# mcremote.net
KiCad netlist of a schematic drawn in EAGLE
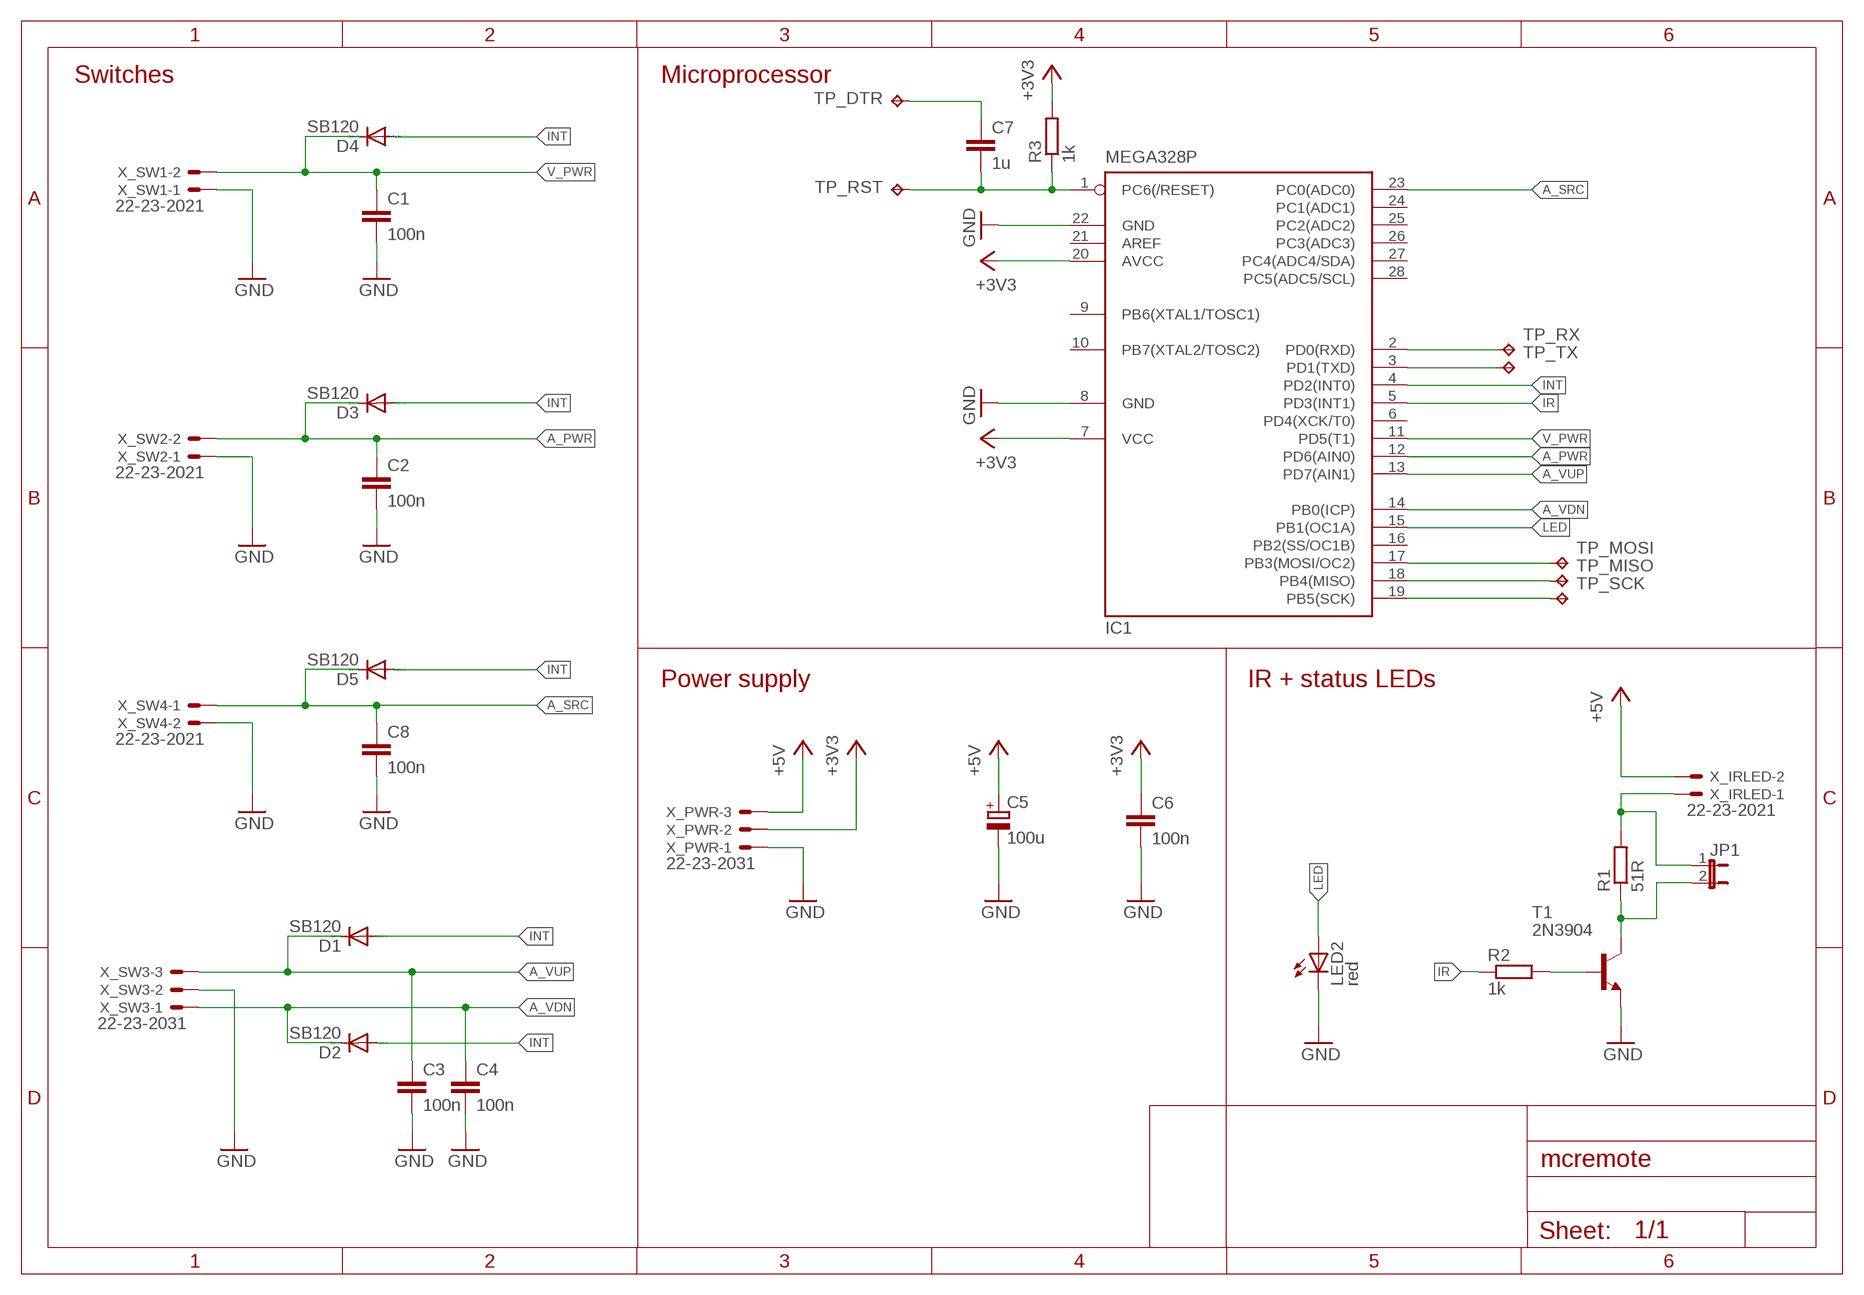
[diagram p0: schematic, sheet 1]

(export (version "E")
  (design (tool "Eeschema 10.0.6"))
  (components
    (comp (ref "C1")
      (value "100n")
      (footprint "eagle-import:C025-024X044")
      (libsource (lib "eagle-import") (part "C-EU025-024X044"))
    )
    (comp (ref "C2")
      (value "100n")
      (footprint "eagle-import:C025-024X044")
      (libsource (lib "eagle-import") (part "C-EU025-024X044"))
    )
    (comp (ref "C3")
      (value "100n")
      (footprint "eagle-import:C025-024X044")
      (libsource (lib "eagle-import") (part "C-EU025-024X044"))
    )
    (comp (ref "C4")
      (value "100n")
      (footprint "eagle-import:C025-024X044")
      (libsource (lib "eagle-import") (part "C-EU025-024X044"))
    )
    (comp (ref "C5")
      (value "100u")
      (footprint "eagle-import:E3,5-8")
      (libsource (lib "eagle-import") (part "CPOL-EUE3.5-8"))
    )
    (comp (ref "C6")
      (value "100n")
      (footprint "eagle-import:C025-024X044")
      (libsource (lib "eagle-import") (part "C-EU025-024X044"))
    )
    (comp (ref "C7")
      (value "1u")
      (footprint "eagle-import:C025-024X044")
      (libsource (lib "eagle-import") (part "C-EU025-024X044"))
    )
    (comp (ref "C8")
      (value "100n")
      (footprint "eagle-import:C025-024X044")
      (libsource (lib "eagle-import") (part "C-EU025-024X044"))
    )
    (comp (ref "D1")
      (value "SB120")
      (footprint "eagle-import:DO41-10")
      (libsource (lib "eagle-import") (part "SB120"))
    )
    (comp (ref "D2")
      (value "SB120")
      (footprint "eagle-import:DO41-10")
      (libsource (lib "eagle-import") (part "SB120"))
    )
    (comp (ref "D3")
      (value "SB120")
      (footprint "eagle-import:DO41-10")
      (libsource (lib "eagle-import") (part "SB120"))
    )
    (comp (ref "D4")
      (value "SB120")
      (footprint "eagle-import:DO41-10")
      (libsource (lib "eagle-import") (part "SB120"))
    )
    (comp (ref "D5")
      (value "SB120")
      (footprint "eagle-import:DO41-7.6")
      (libsource (lib "eagle-import") (part "DIODE-DO41-7.6"))
    )
    (comp (ref "IC1")
      (value "MEGA328P")
      (footprint "eagle-import:DIL28-3")
      (libsource (lib "eagle-import") (part "MEGA8-P"))
    )
    (comp (ref "JP1")
      (value "JP1E")
      (footprint "eagle-import:JP1")
      (libsource (lib "eagle-import") (part "JP1E"))
    )
    (comp (ref "LED2")
      (value "red")
      (footprint "eagle-import:LED3MM")
      (libsource (lib "eagle-import") (part "LED3MM"))
    )
    (comp (ref "R1")
      (value "51R")
      (footprint "eagle-import:0207_7")
      (libsource (lib "eagle-import") (part "R-EU_0207/7"))
    )
    (comp (ref "R2")
      (value "1k")
      (footprint "eagle-import:0207_7")
      (libsource (lib "eagle-import") (part "R-EU_0207/7"))
    )
    (comp (ref "R3")
      (value "1k")
      (footprint "eagle-import:0207_7")
      (libsource (lib "eagle-import") (part "R-EU_0207/7"))
    )
    (comp (ref "T1")
      (value "2N3904")
      (footprint "eagle-import:TO92")
      (libsource (lib "eagle-import") (part "2N3904"))
    )
    (comp (ref "TP_DTR")
      (value "TPPAD1-13")
      (footprint "eagle-import:P1-13")
      (libsource (lib "eagle-import") (part "TPPAD1-13"))
    )
    (comp (ref "TP_MISO")
      (value "TPPAD1-13")
      (footprint "eagle-import:P1-13")
      (libsource (lib "eagle-import") (part "TPPAD1-13"))
    )
    (comp (ref "TP_MOSI")
      (value "TPPAD1-13")
      (footprint "eagle-import:P1-13")
      (libsource (lib "eagle-import") (part "TPPAD1-13"))
    )
    (comp (ref "TP_RST")
      (value "TPPAD1-13")
      (footprint "eagle-import:P1-13")
      (libsource (lib "eagle-import") (part "TPPAD1-13"))
    )
    (comp (ref "TP_RX")
      (value "TPPAD1-13")
      (footprint "eagle-import:P1-13")
      (libsource (lib "eagle-import") (part "TPPAD1-13"))
    )
    (comp (ref "TP_SCK")
      (value "TPPAD1-13")
      (footprint "eagle-import:P1-13")
      (libsource (lib "eagle-import") (part "TPPAD1-13"))
    )
    (comp (ref "TP_TX")
      (value "TPPAD1-13")
      (footprint "eagle-import:P1-13")
      (libsource (lib "eagle-import") (part "TPPAD1-13"))
    )
    (comp (ref "X_IRLED")
      (value "22-23-2021")
      (footprint "eagle-import:22-23-2021")
      (fields (field (name "MF") "MOLEX"))
      (libsource (lib "eagle-import") (part "22-23-2021"))
    )
    (comp (ref "X_PWR")
      (value "22-23-2031")
      (footprint "eagle-import:22-23-2031")
      (fields (field (name "MF") "MOLEX"))
      (libsource (lib "eagle-import") (part "22-23-2031"))
    )
    (comp (ref "X_SW1")
      (value "22-23-2021")
      (footprint "eagle-import:22-23-2021")
      (fields (field (name "MF") "MOLEX"))
      (libsource (lib "eagle-import") (part "22-23-2021"))
    )
    (comp (ref "X_SW2")
      (value "22-23-2021")
      (footprint "eagle-import:22-23-2021")
      (fields (field (name "MF") "MOLEX"))
      (libsource (lib "eagle-import") (part "22-23-2021"))
    )
    (comp (ref "X_SW3")
      (value "22-23-2031")
      (footprint "eagle-import:22-23-2031")
      (fields (field (name "MF") "MOLEX"))
      (libsource (lib "eagle-import") (part "22-23-2031"))
    )
    (comp (ref "X_SW4")
      (value "22-23-2021")
      (footprint "eagle-import:22-23-2021")
      (fields (field (name "MF") "MOLEX"))
      (libsource (lib "eagle-import") (part "22-23-2021"))
    )
  )
  (nets
    (net (code "1") (name "+3V3") (class "Default")
      (node (ref "C6") (pin "1") (pinfunction "1_1") (pintype "passive"))
      (node (ref "IC1") (pin "20") (pinfunction "AVCC_20") (pintype "power_in"))
      (node (ref "IC1") (pin "7") (pinfunction "VCC_7") (pintype "power_in"))
      (node (ref "R3") (pin "2") (pinfunction "2_2") (pintype "passive"))
      (node (ref "X_PWR") (pin "2") (pinfunction "S_2") (pintype "passive"))
    )
    (net (code "2") (name "+5V") (class "Default")
      (node (ref "C5") (pin "+") (pinfunction "+_+") (pintype "passive"))
      (node (ref "X_IRLED") (pin "2") (pinfunction "S_2") (pintype "passive"))
      (node (ref "X_PWR") (pin "3") (pinfunction "S_3") (pintype "passive"))
    )
    (net (code "3") (name "A_PWR") (class "Default")
      (node (ref "C2") (pin "1") (pinfunction "1_1") (pintype "passive"))
      (node (ref "D3") (pin "C") (pinfunction "C_C") (pintype "passive"))
      (node (ref "IC1") (pin "12") (pinfunction "PD6(AIN0)_12") (pintype "bidirectional"))
      (node (ref "X_SW2") (pin "2") (pinfunction "S_2") (pintype "passive"))
    )
    (net (code "4") (name "A_SRC") (class "Default")
      (node (ref "C8") (pin "1") (pinfunction "1_1") (pintype "passive"))
      (node (ref "D5") (pin "C") (pinfunction "C_C") (pintype "passive"))
      (node (ref "IC1") (pin "23") (pinfunction "PC0(ADC0)_23") (pintype "bidirectional"))
      (node (ref "X_SW4") (pin "1") (pinfunction "S_1") (pintype "passive"))
    )
    (net (code "5") (name "A_VDN") (class "Default")
      (node (ref "C4") (pin "1") (pinfunction "1_1") (pintype "passive"))
      (node (ref "D2") (pin "C") (pinfunction "C_C") (pintype "passive"))
      (node (ref "IC1") (pin "14") (pinfunction "PB0(ICP)_14") (pintype "bidirectional"))
      (node (ref "X_SW3") (pin "1") (pinfunction "S_1") (pintype "passive"))
    )
    (net (code "6") (name "A_VUP") (class "Default")
      (node (ref "C3") (pin "1") (pinfunction "1_1") (pintype "passive"))
      (node (ref "D1") (pin "C") (pinfunction "C_C") (pintype "passive"))
      (node (ref "IC1") (pin "13") (pinfunction "PD7(AIN1)_13") (pintype "bidirectional"))
      (node (ref "X_SW3") (pin "3") (pinfunction "S_3") (pintype "passive"))
    )
    (net (code "7") (name "GND") (class "Default")
      (node (ref "C1") (pin "2") (pinfunction "2_2") (pintype "passive"))
      (node (ref "C2") (pin "2") (pinfunction "2_2") (pintype "passive"))
      (node (ref "C3") (pin "2") (pinfunction "2_2") (pintype "passive"))
      (node (ref "C4") (pin "2") (pinfunction "2_2") (pintype "passive"))
      (node (ref "C5") (pin "-") (pinfunction "-_-") (pintype "passive"))
      (node (ref "C6") (pin "2") (pinfunction "2_2") (pintype "passive"))
      (node (ref "C8") (pin "2") (pinfunction "2_2") (pintype "passive"))
      (node (ref "IC1") (pin "22") (pinfunction "GND_22") (pintype "power_in"))
      (node (ref "IC1") (pin "8") (pinfunction "GND_8") (pintype "power_in"))
      (node (ref "LED2") (pin "K") (pinfunction "C_K") (pintype "passive"))
      (node (ref "T1") (pin "3") (pinfunction "E_3") (pintype "passive"))
      (node (ref "X_PWR") (pin "1") (pinfunction "S_1") (pintype "passive"))
      (node (ref "X_SW1") (pin "1") (pinfunction "S_1") (pintype "passive"))
      (node (ref "X_SW2") (pin "1") (pinfunction "S_1") (pintype "passive"))
      (node (ref "X_SW3") (pin "2") (pinfunction "S_2") (pintype "passive"))
      (node (ref "X_SW4") (pin "2") (pinfunction "S_2") (pintype "passive"))
    )
    (net (code "8") (name "INT") (class "Default")
      (node (ref "D1") (pin "A") (pinfunction "A_A") (pintype "passive"))
      (node (ref "D2") (pin "A") (pinfunction "A_A") (pintype "passive"))
      (node (ref "D3") (pin "A") (pinfunction "A_A") (pintype "passive"))
      (node (ref "D4") (pin "A") (pinfunction "A_A") (pintype "passive"))
      (node (ref "D5") (pin "A") (pinfunction "A_A") (pintype "passive"))
      (node (ref "IC1") (pin "4") (pinfunction "PD2(INT0)_4") (pintype "bidirectional"))
    )
    (net (code "9") (name "IR") (class "Default")
      (node (ref "IC1") (pin "5") (pinfunction "PD3(INT1)_5") (pintype "bidirectional"))
      (node (ref "R2") (pin "1") (pinfunction "1_1") (pintype "passive"))
    )
    (net (code "10") (name "LED") (class "Default")
      (node (ref "IC1") (pin "15") (pinfunction "PB1(OC1A)_15") (pintype "bidirectional"))
      (node (ref "LED2") (pin "A") (pinfunction "A_A") (pintype "passive"))
    )
    (net (code "11") (name "Net-(C7-Pad1)") (class "Default")
      (node (ref "C7") (pin "1") (pinfunction "1_1") (pintype "passive"))
      (node (ref "TP_DTR") (pin "TP") (pinfunction "TP_TP") (pintype "input"))
    )
    (net (code "12") (name "Net-(IC1-PB3(MOSI{slash}OC2))") (class "Default")
      (node (ref "IC1") (pin "17") (pinfunction "PB3(MOSI/OC2)_17") (pintype "bidirectional"))
      (node (ref "TP_MOSI") (pin "TP") (pinfunction "TP_TP") (pintype "input"))
    )
    (net (code "13") (name "Net-(IC1-PB4(MISO))") (class "Default")
      (node (ref "IC1") (pin "18") (pinfunction "PB4(MISO)_18") (pintype "bidirectional"))
      (node (ref "TP_MISO") (pin "TP") (pinfunction "TP_TP") (pintype "input"))
    )
    (net (code "14") (name "Net-(IC1-PB5(SCK))") (class "Default")
      (node (ref "IC1") (pin "19") (pinfunction "PB5(SCK)_19") (pintype "bidirectional"))
      (node (ref "TP_SCK") (pin "TP") (pinfunction "TP_TP") (pintype "input"))
    )
    (net (code "15") (name "Net-(IC1-PC6({slash}RESET))") (class "Default")
      (node (ref "C7") (pin "2") (pinfunction "2_2") (pintype "passive"))
      (node (ref "IC1") (pin "1") (pinfunction "PC6(/RESET)_1") (pintype "bidirectional"))
      (node (ref "R3") (pin "1") (pinfunction "1_1") (pintype "passive"))
      (node (ref "TP_RST") (pin "TP") (pinfunction "TP_TP") (pintype "input"))
    )
    (net (code "16") (name "Net-(IC1-PD0(RXD))") (class "Default")
      (node (ref "IC1") (pin "2") (pinfunction "PD0(RXD)_2") (pintype "bidirectional"))
      (node (ref "TP_RX") (pin "TP") (pinfunction "TP_TP") (pintype "input"))
    )
    (net (code "17") (name "Net-(IC1-PD1(TXD))") (class "Default")
      (node (ref "IC1") (pin "3") (pinfunction "PD1(TXD)_3") (pintype "bidirectional"))
      (node (ref "TP_TX") (pin "TP") (pinfunction "TP_TP") (pintype "input"))
    )
    (net (code "18") (name "Net-(T1-B)") (class "Default")
      (node (ref "R2") (pin "2") (pinfunction "2_2") (pintype "passive"))
      (node (ref "T1") (pin "2") (pinfunction "B_2") (pintype "passive"))
    )
    (net (code "19") (name "Net-(T1-C)") (class "Default")
      (node (ref "JP1") (pin "2") (pinfunction "2_2") (pintype "passive"))
      (node (ref "R1") (pin "1") (pinfunction "1_1") (pintype "passive"))
      (node (ref "T1") (pin "1") (pinfunction "C_1") (pintype "passive"))
    )
    (net (code "20") (name "Net-(X_IRLEDA-S)") (class "Default")
      (node (ref "JP1") (pin "1") (pinfunction "1_1") (pintype "passive"))
      (node (ref "R1") (pin "2") (pinfunction "2_2") (pintype "passive"))
      (node (ref "X_IRLED") (pin "1") (pinfunction "S_1") (pintype "passive"))
    )
    (net (code "21") (name "V_PWR") (class "Default")
      (node (ref "C1") (pin "1") (pinfunction "1_1") (pintype "passive"))
      (node (ref "D4") (pin "C") (pinfunction "C_C") (pintype "passive"))
      (node (ref "IC1") (pin "11") (pinfunction "PD5(T1)_11") (pintype "bidirectional"))
      (node (ref "X_SW1") (pin "2") (pinfunction "S_2") (pintype "passive"))
    )
    (net (code "22") (name "unconnected-(IC1-AREF-Pad21)") (class "Default")
      (node (ref "IC1") (pin "21") (pinfunction "AREF_21") (pintype "passive"))
    )
    (net (code "23") (name "unconnected-(IC1-PB2(SS{slash}OC1B)-Pad16)") (class "Default")
      (node (ref "IC1") (pin "16") (pinfunction "PB2(SS/OC1B)_16") (pintype "bidirectional"))
    )
    (net (code "24") (name "unconnected-(IC1-PB6(XTAL1{slash}TOSC1)-Pad9)") (class "Default")
      (node (ref "IC1") (pin "9") (pinfunction "PB6(XTAL1/TOSC1)_9") (pintype "bidirectional"))
    )
    (net (code "25") (name "unconnected-(IC1-PB7(XTAL2{slash}TOSC2)-Pad10)") (class "Default")
      (node (ref "IC1") (pin "10") (pinfunction "PB7(XTAL2/TOSC2)_10") (pintype "bidirectional"))
    )
    (net (code "26") (name "unconnected-(IC1-PC1(ADC1)-Pad24)") (class "Default")
      (node (ref "IC1") (pin "24") (pinfunction "PC1(ADC1)_24") (pintype "bidirectional"))
    )
    (net (code "27") (name "unconnected-(IC1-PC2(ADC2)-Pad25)") (class "Default")
      (node (ref "IC1") (pin "25") (pinfunction "PC2(ADC2)_25") (pintype "bidirectional"))
    )
    (net (code "28") (name "unconnected-(IC1-PC3(ADC3)-Pad26)") (class "Default")
      (node (ref "IC1") (pin "26") (pinfunction "PC3(ADC3)_26") (pintype "bidirectional"))
    )
    (net (code "29") (name "unconnected-(IC1-PC4(ADC4{slash}SDA)-Pad27)") (class "Default")
      (node (ref "IC1") (pin "27") (pinfunction "PC4(ADC4/SDA)_27") (pintype "bidirectional"))
    )
    (net (code "30") (name "unconnected-(IC1-PC5(ADC5{slash}SCL)-Pad28)") (class "Default")
      (node (ref "IC1") (pin "28") (pinfunction "PC5(ADC5/SCL)_28") (pintype "bidirectional"))
    )
    (net (code "31") (name "unconnected-(IC1-PD4(XCK{slash}T0)-Pad6)") (class "Default")
      (node (ref "IC1") (pin "6") (pinfunction "PD4(XCK/T0)_6") (pintype "bidirectional"))
    )
  )
)
